# MCU.net
KiCad netlist of a schematic drawn in Altium Designer
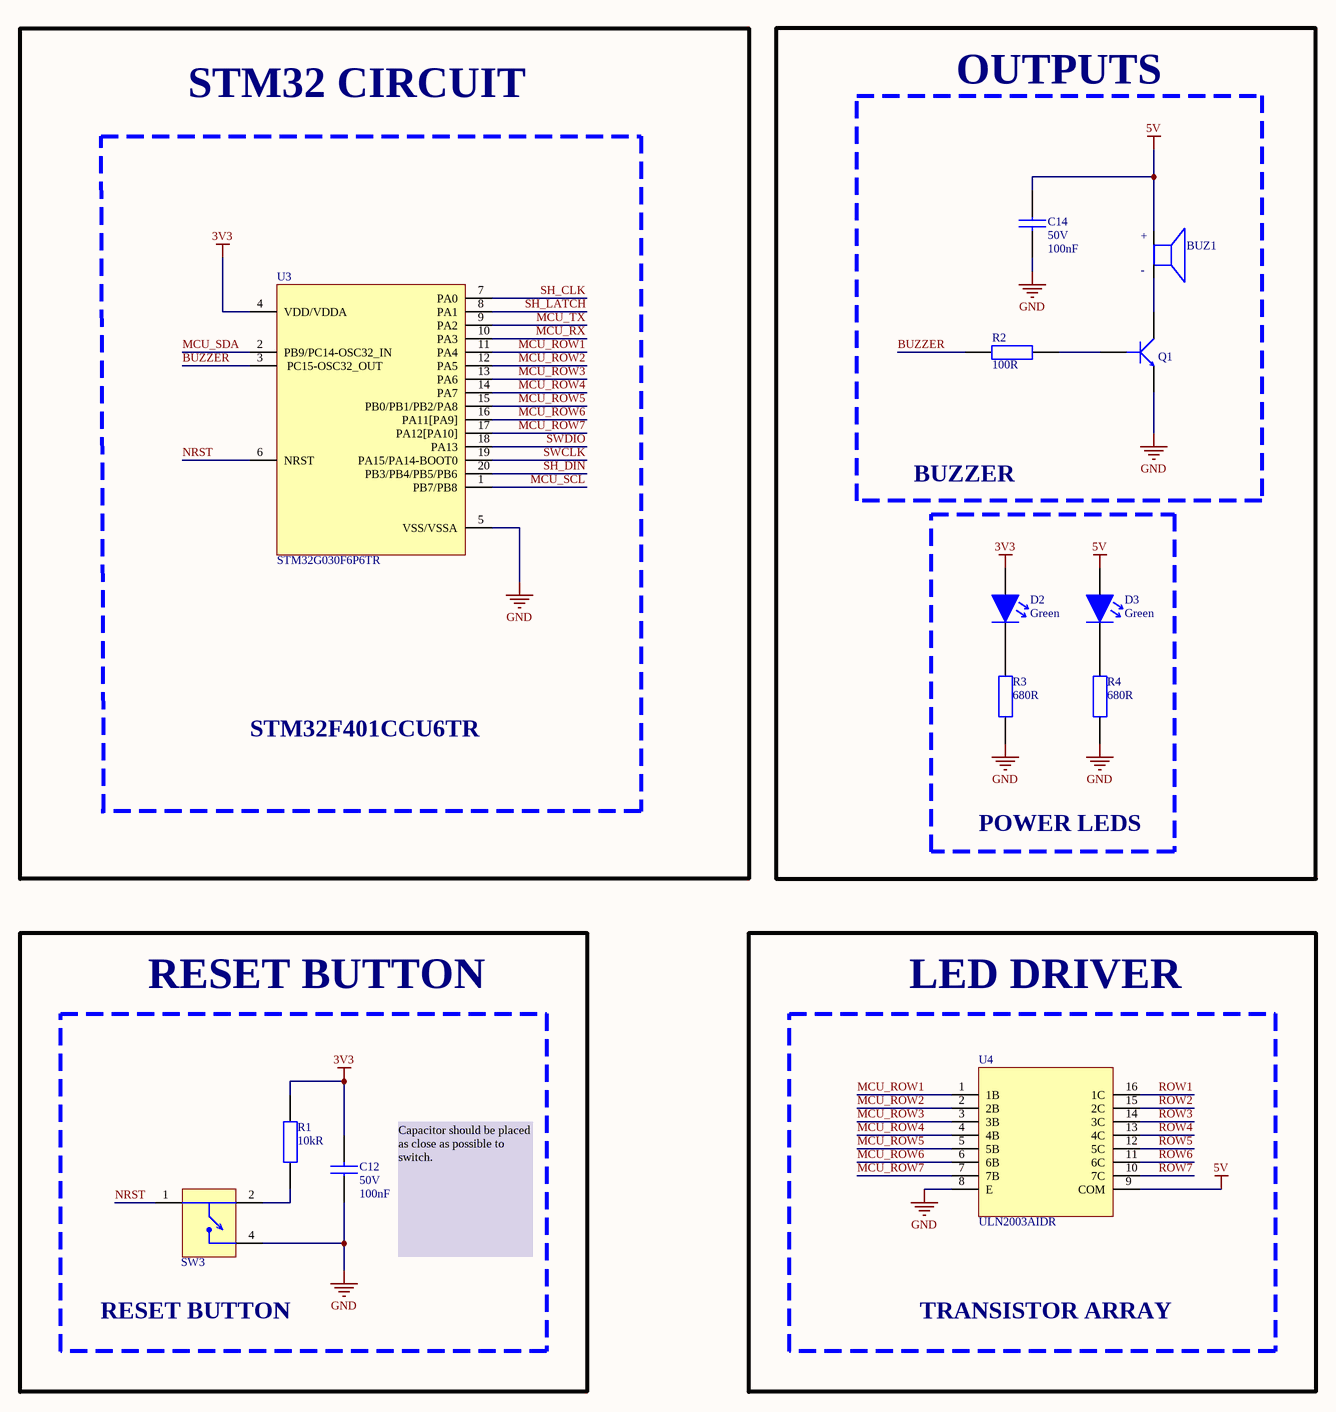
[diagram p0: MCU.SchDoc]

(export (version "E")
  (design (tool "Eeschema 10.0.6"))
  (components
    (comp (ref "BUZ1")
      (value "SMI-1027-TW-5V-R")
      (footprint "BUZZER_SMD")
      (description "Audio Indicator 5V 30mA 80dBA 2.7KHz Resonant Frequency SMD")
      (fields (field (name "MANUFACTURER") "Projects Unlimited") (field (name "DESIGNEDBY") "Aslı Kurt"))
      (libsource (lib "MyLibrary") (part "BUZZER_5V_SMD"))
    )
    (comp (ref "C12")
      (value "C0603C104K5RACTU")
      (footprint "CAP_0603")
      (description "CAP CER 100nF %10 0603 SMD")
      (fields
        (field (name "MANUFACTURER") "KEMET")
        (field (name "TOLERANCE") "10%")
        (field (name "VOLTAGE RATING (DC)") "50V")
        (field (name "CAPACITANCE") "100nF")
        (field (name "DESIGNEDBY") "Aslı Kurt")
      )
      (libsource (lib "MyLibrary") (part "CAP CER 100nF 0603"))
    )
    (comp (ref "C14")
      (value "C0603C104K5RACTU")
      (footprint "CAP_0603")
      (description "CAP CER 100nF %10 0603 SMD")
      (fields
        (field (name "MANUFACTURER") "KEMET")
        (field (name "TOLERANCE") "10%")
        (field (name "VOLTAGE RATING (DC)") "50V")
        (field (name "CAPACITANCE") "100nF")
        (field (name "DESIGNEDBY") "Aslı Kurt")
      )
      (libsource (lib "MyLibrary") (part "CAP CER 100nF 0603"))
    )
    (comp (ref "D2")
      (value "LTST-C171GKT")
      (footprint "LED_GREEN_0805")
      (description "Green 0805 130 º Min 5 mcd Typical 12 mcd Water Clear Lens SMT LED")
      (fields
        (field (name "MANUFACTURER") "Vishay Lite-On")
        (field (name "COLOR") "Green")
        (field (name "DESIGNEDBY") "Aslı Kurt")
      )
      (libsource (lib "MyLibrary") (part "LED GREEN 0805"))
    )
    (comp (ref "D3")
      (value "LTST-C171GKT")
      (footprint "LED_GREEN_0805")
      (description "Green 0805 130 º Min 5 mcd Typical 12 mcd Water Clear Lens SMT LED")
      (fields
        (field (name "MANUFACTURER") "Vishay Lite-On")
        (field (name "COLOR") "Green")
        (field (name "DESIGNEDBY") "Aslı Kurt")
      )
      (libsource (lib "MyLibrary") (part "LED GREEN 0805"))
    )
    (comp (ref "Q1")
      (value "MMBT3904-7-F")
      (footprint "SOT-23F")
      (description "Transistor General Purpose BJT NPN 40 Volt 0.2A Automotive 3-Pin SOT-23")
      (fields (field (name "MANUFACTURER") "Diodes Zetex") (field (name "DESIGNEDBY") "Aslı Kurt"))
      (libsource (lib "MyLibrary") (part "MMBT3904-7-F"))
    )
    (comp (ref "R1")
      (value "RC0805JR-0710KL")
      (footprint "RES_0805")
      (description "RES 10K OHM 5% 1/8W 0805")
      (fields
        (field (name "MANUFACTURER") "Yageo")
        (field (name "TOLERANCE") "5%")
        (field (name "RESISTANCE") "10kR")
        (field (name "DESIGNEDBY") "Aslı Kurt")
      )
      (libsource (lib "MyLibrary") (part "RES 10K OHM 08051/8W"))
    )
    (comp (ref "R2")
      (value "RC0603JR-07100RL")
      (footprint "RES_0603")
      (description "RES 100 %5 OHM 0603 SMD")
      (fields
        (field (name "MANUFACTURER") "Yageo")
        (field (name "TOLERANCE") "5%")
        (field (name "RESISTANCE") "100R")
        (field (name "DESIGNEDBY") "Aslı Kurt")
      )
      (libsource (lib "MyLibrary") (part "RES 100 OHM 0603 1/10W"))
    )
    (comp (ref "R3")
      (value "RC1206FR-07680RL")
      (footprint "RES_1206")
      (description "SMD Chip Resistor, 680 Ohm, ï¿½ 1%, 250 mW, 1206 [3216 Metric], Thick Film, General Purpose")
      (fields
        (field (name "MANUFACTURER") "Yageo")
        (field (name "RESISTANCE") "680R")
        (field (name "DESIGNEDBY") "Aslı Kurt")
      )
      (libsource (lib "MyLibrary") (part "RES 680 OHM 1206 1/4W"))
    )
    (comp (ref "R4")
      (value "RC1206FR-07680RL")
      (footprint "RES_1206")
      (description "SMD Chip Resistor, 680 Ohm, ï¿½ 1%, 250 mW, 1206 [3216 Metric], Thick Film, General Purpose")
      (fields
        (field (name "MANUFACTURER") "Yageo")
        (field (name "RESISTANCE") "680R")
        (field (name "DESIGNEDBY") "Aslı Kurt")
      )
      (libsource (lib "MyLibrary") (part "RES 680 OHM 1206 1/4W"))
    )
    (comp (ref "SW3")
      (value "PTS815 SJK 250 SMTR LFS")
      (footprint "BUTTON SMD")
      (description "Microminiature Top Actuated Tactile Switch Momentary SPST-NO 50mA 12VDC Surface Mount T/R")
      (fields
        (field (name "MANUFACTURER") "ITT C&K")
        (field (name "MANUFACTURER PART NUMBER") "PTS815SJK250SMTRLFS")
        (field (name "DESIGNEDBY") "Aslı Kurt")
      )
      (libsource (lib "MyLibrary") (part "4.2mm x 3.2mm BUTTON"))
    )
    (comp (ref "U3")
      (value "STM32G030F6P6TR")
      (footprint "TSSOP20")
      (description "MCU 32-bit ARM Cortex M0+ RISC 32KB Flash 2.5V/3.3V 20-Pin TSSOP T/R")
      (fields (field (name "MANUFACTURER") "STMicroelectronics") (field (name "DESIGNEDBY") "Aslı Kurt"))
      (libsource (lib "MyLibrary") (part "STM32G030F6P6TR"))
    )
    (comp (ref "U4")
      (value "ULN2003AIDR")
      (footprint "16-SOIC")
      (description "50-V, 7-ch darlington transistor array, -40 to 105C 16-SOIC -40 to 105")
      (fields (field (name "MANUFACTURER") "Texas Instruments") (field (name "DESIGNEDBY") "Aslı Kurt"))
      (libsource (lib "MyLibrary") (part "ULN2003AIDR"))
    )
  )
  (nets
    (net (code "1") (name "/BUZZER") (class "Default")
      (node (ref "R2") (pin "1") (pinfunction "1_1") (pintype "passive"))
      (node (ref "U3") (pin "3") (pinfunction "_PC15-OSC32_OUT_3") (pintype "passive"))
    )
    (net (code "2") (name "/MCU_ROW1") (class "Default")
      (node (ref "U3") (pin "11") (pinfunction "PA4_11") (pintype "passive"))
      (node (ref "U4") (pin "1") (pinfunction "1B_1") (pintype "passive"))
    )
    (net (code "3") (name "/MCU_ROW2") (class "Default")
      (node (ref "U3") (pin "12") (pinfunction "PA5_12") (pintype "passive"))
      (node (ref "U4") (pin "2") (pinfunction "2B_2") (pintype "passive"))
    )
    (net (code "4") (name "/MCU_ROW3") (class "Default")
      (node (ref "U3") (pin "13") (pinfunction "PA6_13") (pintype "passive"))
      (node (ref "U4") (pin "3") (pinfunction "3B_3") (pintype "passive"))
    )
    (net (code "5") (name "/MCU_ROW4") (class "Default")
      (node (ref "U3") (pin "14") (pinfunction "PA7_14") (pintype "passive"))
      (node (ref "U4") (pin "4") (pinfunction "4B_4") (pintype "passive"))
    )
    (net (code "6") (name "/MCU_ROW5") (class "Default")
      (node (ref "U3") (pin "15") (pinfunction "PB0/PB1/PB2/PA8_15") (pintype "passive"))
      (node (ref "U4") (pin "5") (pinfunction "5B_5") (pintype "passive"))
    )
    (net (code "7") (name "/MCU_ROW6") (class "Default")
      (node (ref "U3") (pin "16") (pinfunction "PA11[PA9]_16") (pintype "passive"))
      (node (ref "U4") (pin "6") (pinfunction "6B_6") (pintype "passive"))
    )
    (net (code "8") (name "/MCU_ROW7") (class "Default")
      (node (ref "U3") (pin "17") (pinfunction "PA12[PA10]_17") (pintype "passive"))
      (node (ref "U4") (pin "7") (pinfunction "7B_7") (pintype "passive"))
    )
    (net (code "9") (name "/MCU_RX") (class "Default")
      (node (ref "U3") (pin "10") (pinfunction "PA3_10") (pintype "passive"))
    )
    (net (code "10") (name "/MCU_SCL") (class "Default")
      (node (ref "U3") (pin "1") (pinfunction "PB7/PB8_1") (pintype "passive"))
    )
    (net (code "11") (name "/MCU_SDA") (class "Default")
      (node (ref "U3") (pin "2") (pinfunction "PB9/PC14-OSC32_IN_2") (pintype "passive"))
    )
    (net (code "12") (name "/MCU_TX") (class "Default")
      (node (ref "U3") (pin "9") (pinfunction "PA2_9") (pintype "passive"))
    )
    (net (code "13") (name "/NRST") (class "Default")
      (node (ref "SW3") (pin "1") (pinfunction "1_1") (pintype "passive"))
      (node (ref "U3") (pin "6") (pinfunction "NRST_6") (pintype "passive"))
    )
    (net (code "14") (name "/ROW1") (class "Default")
      (node (ref "U4") (pin "16") (pinfunction "1C_16") (pintype "passive"))
    )
    (net (code "15") (name "/ROW2") (class "Default")
      (node (ref "U4") (pin "15") (pinfunction "2C_15") (pintype "passive"))
    )
    (net (code "16") (name "/ROW3") (class "Default")
      (node (ref "U4") (pin "14") (pinfunction "3C_14") (pintype "passive"))
    )
    (net (code "17") (name "/ROW4") (class "Default")
      (node (ref "U4") (pin "13") (pinfunction "4C_13") (pintype "passive"))
    )
    (net (code "18") (name "/ROW5") (class "Default")
      (node (ref "U4") (pin "12") (pinfunction "5C_12") (pintype "passive"))
    )
    (net (code "19") (name "/ROW6") (class "Default")
      (node (ref "U4") (pin "11") (pinfunction "6C_11") (pintype "passive"))
    )
    (net (code "20") (name "/ROW7") (class "Default")
      (node (ref "U4") (pin "10") (pinfunction "7C_10") (pintype "passive"))
    )
    (net (code "21") (name "/SH_CLK") (class "Default")
      (node (ref "U3") (pin "7") (pinfunction "PA0_7") (pintype "passive"))
    )
    (net (code "22") (name "/SH_DIN") (class "Default")
      (node (ref "U3") (pin "20") (pinfunction "PB3/PB4/PB5/PB6_20") (pintype "passive"))
    )
    (net (code "23") (name "/SH_LATCH") (class "Default")
      (node (ref "U3") (pin "8") (pinfunction "PA1_8") (pintype "passive"))
    )
    (net (code "24") (name "/SWCLK") (class "Default")
      (node (ref "U3") (pin "19") (pinfunction "PA15/PA14-BOOT0_19") (pintype "passive"))
    )
    (net (code "25") (name "/SWDIO") (class "Default")
      (node (ref "U3") (pin "18") (pinfunction "PA13_18") (pintype "passive"))
    )
    (net (code "26") (name "3V3") (class "Default")
      (node (ref "C12") (pin "2") (pinfunction "2_2") (pintype "passive"))
      (node (ref "D2") (pin "1") (pinfunction "1_1") (pintype "power_in"))
      (node (ref "R1") (pin "2") (pinfunction "2_2") (pintype "passive"))
      (node (ref "U3") (pin "4") (pinfunction "VDD/VDDA_4") (pintype "passive"))
    )
    (net (code "27") (name "5V") (class "Default")
      (node (ref "BUZ1") (pin "P") (pinfunction "POS_P") (pintype "passive"))
      (node (ref "C14") (pin "1") (pinfunction "1_1") (pintype "passive"))
      (node (ref "D3") (pin "1") (pinfunction "1_1") (pintype "power_in"))
      (node (ref "U4") (pin "9") (pinfunction "COM_9") (pintype "passive"))
    )
    (net (code "28") (name "GND") (class "Default")
      (node (ref "C12") (pin "1") (pinfunction "1_1") (pintype "passive"))
      (node (ref "C14") (pin "2") (pinfunction "2_2") (pintype "passive"))
      (node (ref "Q1") (pin "2") (pinfunction "E_2") (pintype "power_in"))
      (node (ref "R3") (pin "1") (pinfunction "1_1") (pintype "passive"))
      (node (ref "R4") (pin "1") (pinfunction "1_1") (pintype "passive"))
      (node (ref "SW3") (pin "4") (pinfunction "4_4") (pintype "passive"))
      (node (ref "U3") (pin "5") (pinfunction "VSS/VSSA_5") (pintype "passive"))
      (node (ref "U4") (pin "8") (pinfunction "E_8") (pintype "passive"))
    )
    (net (code "29") (name "Net-(BUZ1-NEG)") (class "Default")
      (node (ref "BUZ1") (pin "N") (pinfunction "NEG_N") (pintype "passive"))
      (node (ref "Q1") (pin "3") (pinfunction "C_3") (pintype "power_in"))
    )
    (net (code "30") (name "Net-(D2-Pad2)") (class "Default")
      (node (ref "D2") (pin "2") (pinfunction "2_2") (pintype "power_in"))
      (node (ref "R3") (pin "2") (pinfunction "2_2") (pintype "passive"))
    )
    (net (code "31") (name "Net-(D3-Pad2)") (class "Default")
      (node (ref "D3") (pin "2") (pinfunction "2_2") (pintype "power_in"))
      (node (ref "R4") (pin "2") (pinfunction "2_2") (pintype "passive"))
    )
    (net (code "32") (name "Net-(Q1-B)") (class "Default")
      (node (ref "Q1") (pin "1") (pinfunction "B_1") (pintype "power_in"))
      (node (ref "R2") (pin "2") (pinfunction "2_2") (pintype "passive"))
    )
    (net (code "33") (name "Net-(R1-Pad1)") (class "Default")
      (node (ref "R1") (pin "1") (pinfunction "1_1") (pintype "passive"))
      (node (ref "SW3") (pin "2") (pinfunction "2_2") (pintype "passive"))
    )
  )
)
